# 3_mpcie.net
KiCad netlist of a schematic drawn in Altium Designer
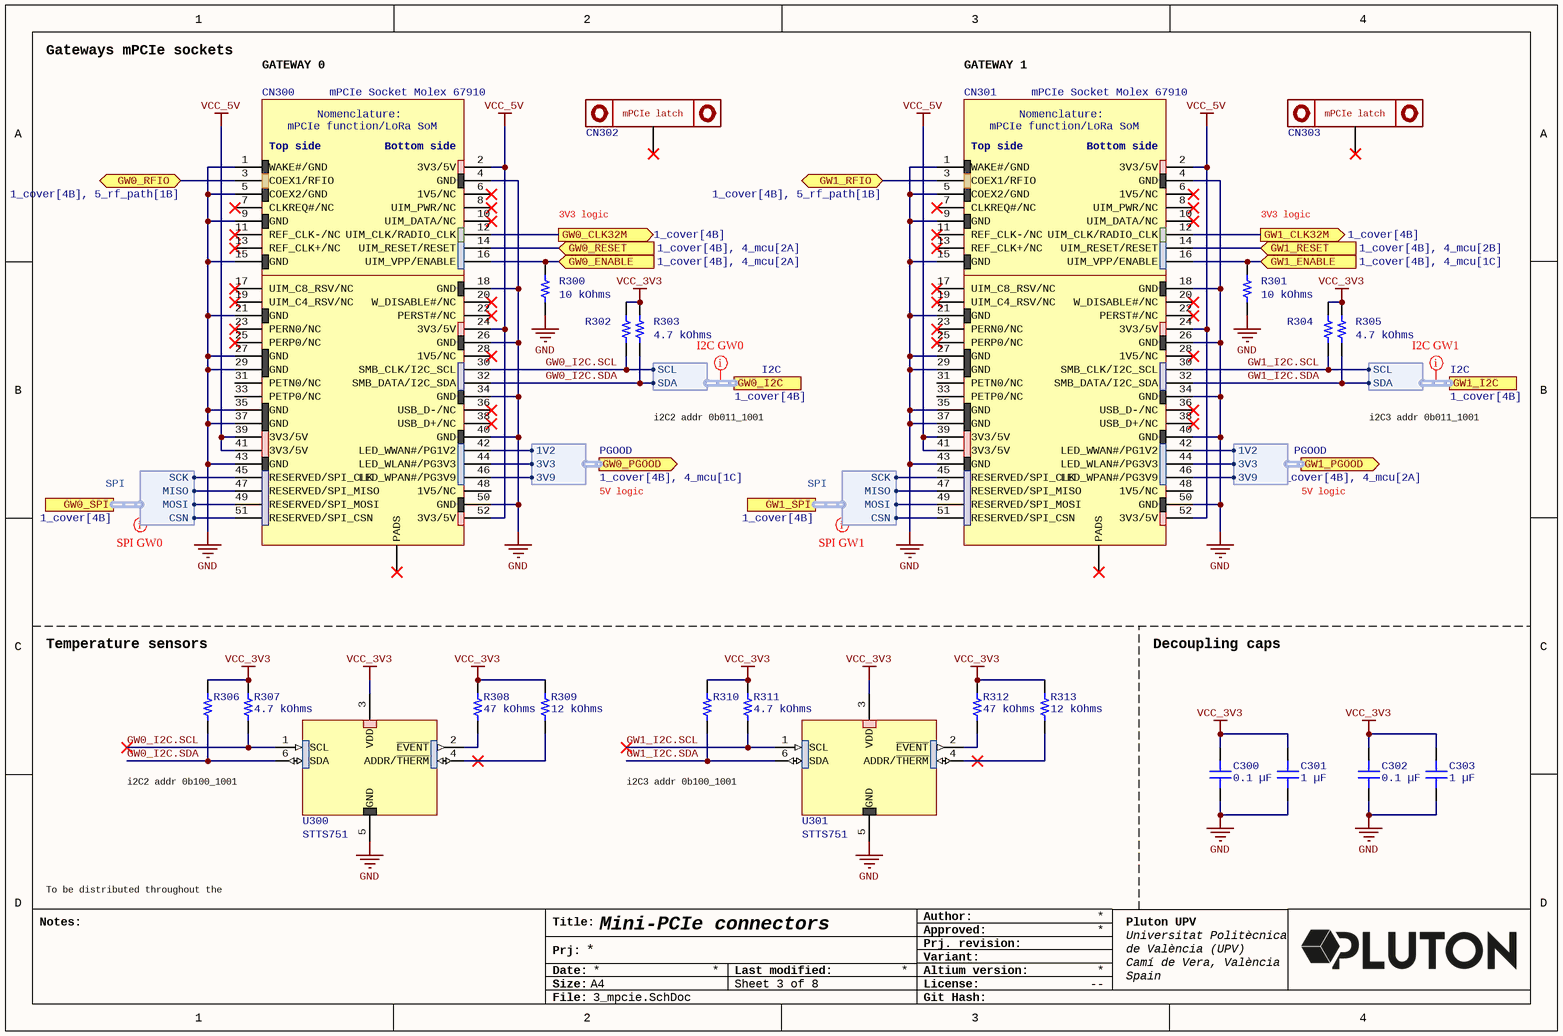
[diagram p0: 3_mpcie.SchDoc]

(export (version "E")
  (design (tool "Eeschema 10.0.6"))
  (components
    (comp (ref "C300")
      (value "0.1 µF")
      (footprint "CAP 0402_1005")
      (description "CAP CER 0402 0.1UF 16V X7R 10%")
      (fields (field (name "PART NUMBER") "C0402C104K4RECAUTO") (field (name "MANUFACTURER") "KEMET"))
      (libsource (lib "Celestial Altium Library - altium_library") (part "Capacitor"))
    )
    (comp (ref "C301")
      (value "1 µF")
      (footprint "CAP 0402_1005")
      (description "CAP CER 1UF 10V X7S 0402")
      (fields
        (field (name "PART NUMBER") "GRT155C71A105KE13D")
        (field (name "MANUFACTURER") "Murata Electronics")
      )
      (libsource (lib "Celestial Altium Library - altium_library") (part "Capacitor"))
    )
    (comp (ref "C302")
      (value "0.1 µF")
      (footprint "CAP 0402_1005")
      (description "CAP CER 0402 0.1UF 16V X7R 10%")
      (fields (field (name "PART NUMBER") "C0402C104K4RECAUTO") (field (name "MANUFACTURER") "KEMET"))
      (libsource (lib "Celestial Altium Library - altium_library") (part "Capacitor"))
    )
    (comp (ref "C303")
      (value "1 µF")
      (footprint "CAP 0402_1005")
      (description "CAP CER 1UF 10V X7S 0402")
      (fields
        (field (name "PART NUMBER") "GRT155C71A105KE13D")
        (field (name "MANUFACTURER") "Murata Electronics")
      )
      (libsource (lib "Celestial Altium Library - altium_library") (part "Capacitor"))
    )
    (comp (ref "CN300")
      (value "mPCIe Socket Molex 67910")
      (footprint "mpcie:mPCIe Socket Molex 67910")
      (libsource (lib "mpcie") (part "MiniPCIe Socket"))
    )
    (comp (ref "CN301")
      (value "mPCIe Socket Molex 67910")
      (footprint "mpcie:mPCIe Socket Molex 67910")
      (libsource (lib "mpcie") (part "MiniPCIe Socket"))
    )
    (comp (ref "CN302")
      (value "mPCIe Latch Molex 48099")
      (footprint "mpcie:MPCIE LATCH MOLEX 48099")
      (libsource (lib "mpcie") (part "MiniPCIe Socket latch"))
    )
    (comp (ref "CN303")
      (value "mPCIe Latch Molex 48099")
      (footprint "mpcie:MPCIE LATCH MOLEX 48099")
      (libsource (lib "mpcie") (part "MiniPCIe Socket latch"))
    )
    (comp (ref "R300")
      (value "10 kOhms")
      (footprint "RES 0201_0603")
      (description "RES SMD 10K OHM 1% 1/20W 0201")
      (fields (field (name "PART NUMBER") "AF0201FR-0710KL") (field (name "MANUFACTURER") "Yageo"))
      (libsource (lib "Celestial Altium Library - altium_library") (part "Resistor"))
    )
    (comp (ref "R301")
      (value "10 kOhms")
      (footprint "RES 0201_0603")
      (description "RES SMD 10K OHM 1% 1/20W 0201")
      (fields (field (name "PART NUMBER") "AF0201FR-0710KL") (field (name "MANUFACTURER") "Yageo"))
      (libsource (lib "Celestial Altium Library - altium_library") (part "Resistor"))
    )
    (comp (ref "R302")
      (value "4.7 kOhms")
      (footprint "RES 0201_0603")
      (description "RES SMD 4.7K OHM 1% 1/20W 0201")
      (fields (field (name "PART NUMBER") "AC0201FR-074K7L") (field (name "MANUFACTURER") "Yageo"))
      (libsource (lib "Celestial Altium Library - altium_library") (part "Resistor"))
    )
    (comp (ref "R303")
      (value "4.7 kOhms")
      (footprint "RES 0201_0603")
      (description "RES SMD 4.7K OHM 1% 1/20W 0201")
      (fields (field (name "PART NUMBER") "AC0201FR-074K7L") (field (name "MANUFACTURER") "Yageo"))
      (libsource (lib "Celestial Altium Library - altium_library") (part "Resistor"))
    )
    (comp (ref "R304")
      (value "4.7 kOhms")
      (footprint "RES 0201_0603")
      (description "RES SMD 4.7K OHM 1% 1/20W 0201")
      (fields (field (name "PART NUMBER") "AC0201FR-074K7L") (field (name "MANUFACTURER") "Yageo"))
      (libsource (lib "Celestial Altium Library - altium_library") (part "Resistor"))
    )
    (comp (ref "R305")
      (value "4.7 kOhms")
      (footprint "RES 0201_0603")
      (description "RES SMD 4.7K OHM 1% 1/20W 0201")
      (fields (field (name "PART NUMBER") "AC0201FR-074K7L") (field (name "MANUFACTURER") "Yageo"))
      (libsource (lib "Celestial Altium Library - altium_library") (part "Resistor"))
    )
    (comp (ref "R306")
      (value "4.7 kOhms")
      (footprint "RES 0201_0603")
      (description "RES SMD 4.7K OHM 1% 1/20W 0201")
      (fields (field (name "PART NUMBER") "AC0201FR-074K7L") (field (name "MANUFACTURER") "Yageo"))
      (libsource (lib "Celestial Altium Library - altium_library") (part "Resistor"))
    )
    (comp (ref "R307")
      (value "4.7 kOhms")
      (footprint "RES 0201_0603")
      (description "RES SMD 4.7K OHM 1% 1/20W 0201")
      (fields (field (name "PART NUMBER") "AC0201FR-074K7L") (field (name "MANUFACTURER") "Yageo"))
      (libsource (lib "Celestial Altium Library - altium_library") (part "Resistor"))
    )
    (comp (ref "R308")
      (value "47 kOhms")
      (footprint "RES 0201_0603")
      (description "RES SMD 47K OHM 1% 1/20W 0201")
      (fields (field (name "PART NUMBER") "AC0201FR-0747KL") (field (name "MANUFACTURER") "Yageo"))
      (libsource (lib "Celestial Altium Library - altium_library") (part "Resistor"))
    )
    (comp (ref "R309")
      (value "12 kOhms")
      (footprint "RES 0201_0603")
      (description "RES SMD 12K OHM 1% 1/20W 0201")
      (fields (field (name "PART NUMBER") "CRCW020112K0FNED") (field (name "MANUFACTURER") "Vishay Dale"))
      (libsource (lib "Celestial Altium Library - altium_library") (part "Resistor"))
    )
    (comp (ref "R310")
      (value "4.7 kOhms")
      (footprint "RES 0201_0603")
      (description "RES SMD 4.7K OHM 1% 1/20W 0201")
      (fields (field (name "PART NUMBER") "AC0201FR-074K7L") (field (name "MANUFACTURER") "Yageo"))
      (libsource (lib "Celestial Altium Library - altium_library") (part "Resistor"))
    )
    (comp (ref "R311")
      (value "4.7 kOhms")
      (footprint "RES 0201_0603")
      (description "RES SMD 4.7K OHM 1% 1/20W 0201")
      (fields (field (name "PART NUMBER") "AC0201FR-074K7L") (field (name "MANUFACTURER") "Yageo"))
      (libsource (lib "Celestial Altium Library - altium_library") (part "Resistor"))
    )
    (comp (ref "R312")
      (value "47 kOhms")
      (footprint "RES 0201_0603")
      (description "RES SMD 47K OHM 1% 1/20W 0201")
      (fields (field (name "PART NUMBER") "AC0201FR-0747KL") (field (name "MANUFACTURER") "Yageo"))
      (libsource (lib "Celestial Altium Library - altium_library") (part "Resistor"))
    )
    (comp (ref "R313")
      (value "12 kOhms")
      (footprint "RES 0201_0603")
      (description "RES SMD 12K OHM 1% 1/20W 0201")
      (fields (field (name "PART NUMBER") "CRCW020112K0FNED") (field (name "MANUFACTURER") "Vishay Dale"))
      (libsource (lib "Celestial Altium Library - altium_library") (part "Resistor"))
    )
    (comp (ref "U300")
      (value "STTS751")
      (footprint "ics:UDFN-6L")
      (description "2.25 V low-voltage local digital temperature sensor")
      (libsource (lib "sensors") (part "STTS751"))
    )
    (comp (ref "U301")
      (value "STTS751")
      (footprint "ics:UDFN-6L")
      (description "2.25 V low-voltage local digital temperature sensor")
      (libsource (lib "sensors") (part "STTS751"))
    )
  )
  (nets
    (net (code "4") (name "/GW0_CLK32M") (class "Default")
      (node (ref "CN300") (pin "12") (pinfunction "UIM_CLK/RADIO_CLK_12") (pintype "passive"))
    )
    (net (code "5") (name "/GW0_ENABLE") (class "Default")
      (node (ref "CN300") (pin "16") (pinfunction "UIM_VPP/ENABLE_16") (pintype "passive"))
      (node (ref "R300") (pin "2") (pinfunction "2_2") (pintype "passive"))
    )
    (net (code "6") (name "/GW0_I2C.SCL") (class "Default")
      (node (ref "CN300") (pin "30") (pinfunction "SMB_CLK/I2C_SCL_30") (pintype "passive"))
      (node (ref "R302") (pin "1") (pinfunction "1_1") (pintype "passive"))
      (node (ref "R307") (pin "1") (pinfunction "1_1") (pintype "passive"))
      (node (ref "U300") (pin "1") (pinfunction "SCL_1") (pintype "input"))
    )
    (net (code "7") (name "/GW0_I2C.SDA") (class "Default")
      (node (ref "CN300") (pin "32") (pinfunction "SMB_DATA/I2C_SDA_32") (pintype "passive"))
      (node (ref "R303") (pin "1") (pinfunction "1_1") (pintype "passive"))
      (node (ref "R306") (pin "1") (pinfunction "1_1") (pintype "passive"))
      (node (ref "U300") (pin "6") (pinfunction "SDA_6") (pintype "bidirectional"))
    )
    (net (code "8") (name "/GW0_RESET") (class "Default")
      (node (ref "CN300") (pin "14") (pinfunction "UIM_RESET/RESET_14") (pintype "passive"))
    )
    (net (code "9") (name "/GW0_RFIO") (class "Default")
      (node (ref "CN300") (pin "3") (pinfunction "COEX1/RFIO_3") (pintype "passive"))
    )
    (net (code "10") (name "/GW1_CLK32M") (class "Default")
      (node (ref "CN301") (pin "12") (pinfunction "UIM_CLK/RADIO_CLK_12") (pintype "passive"))
    )
    (net (code "11") (name "/GW1_ENABLE") (class "Default")
      (node (ref "CN301") (pin "16") (pinfunction "UIM_VPP/ENABLE_16") (pintype "passive"))
      (node (ref "R301") (pin "2") (pinfunction "2_2") (pintype "passive"))
    )
    (net (code "12") (name "/GW1_I2C.SCL") (class "Default")
      (node (ref "CN301") (pin "30") (pinfunction "SMB_CLK/I2C_SCL_30") (pintype "passive"))
      (node (ref "R304") (pin "1") (pinfunction "1_1") (pintype "passive"))
      (node (ref "R311") (pin "1") (pinfunction "1_1") (pintype "passive"))
      (node (ref "U301") (pin "1") (pinfunction "SCL_1") (pintype "input"))
    )
    (net (code "13") (name "/GW1_I2C.SDA") (class "Default")
      (node (ref "CN301") (pin "32") (pinfunction "SMB_DATA/I2C_SDA_32") (pintype "passive"))
      (node (ref "R305") (pin "1") (pinfunction "1_1") (pintype "passive"))
      (node (ref "R310") (pin "1") (pinfunction "1_1") (pintype "passive"))
      (node (ref "U301") (pin "6") (pinfunction "SDA_6") (pintype "bidirectional"))
    )
    (net (code "14") (name "/GW1_RESET") (class "Default")
      (node (ref "CN301") (pin "14") (pinfunction "UIM_RESET/RESET_14") (pintype "passive"))
    )
    (net (code "15") (name "/GW1_RFIO") (class "Default")
      (node (ref "CN301") (pin "3") (pinfunction "COEX1/RFIO_3") (pintype "passive"))
    )
    (net (code "19") (name "GND") (class "Default")
      (node (ref "C300") (pin "1") (pinfunction "1_1") (pintype "passive"))
      (node (ref "C301") (pin "1") (pinfunction "1_1") (pintype "passive"))
      (node (ref "C302") (pin "1") (pinfunction "1_1") (pintype "passive"))
      (node (ref "C303") (pin "1") (pinfunction "1_1") (pintype "passive"))
      (node (ref "CN300") (pin "1") (pinfunction "WAKE#/GND_1") (pintype "passive"))
      (node (ref "CN300") (pin "15") (pinfunction "GND_15") (pintype "power_in"))
      (node (ref "CN300") (pin "18") (pinfunction "GND_18") (pintype "power_in"))
      (node (ref "CN300") (pin "21") (pinfunction "GND_21") (pintype "power_in"))
      (node (ref "CN300") (pin "26") (pinfunction "GND_26") (pintype "power_in"))
      (node (ref "CN300") (pin "27") (pinfunction "GND_27") (pintype "power_in"))
      (node (ref "CN300") (pin "29") (pinfunction "GND_29") (pintype "power_in"))
      (node (ref "CN300") (pin "34") (pinfunction "GND_34") (pintype "power_in"))
      (node (ref "CN300") (pin "35") (pinfunction "GND_35") (pintype "power_in"))
      (node (ref "CN300") (pin "37") (pinfunction "GND_37") (pintype "power_in"))
      (node (ref "CN300") (pin "4") (pinfunction "GND_4") (pintype "power_in"))
      (node (ref "CN300") (pin "40") (pinfunction "GND_40") (pintype "power_in"))
      (node (ref "CN300") (pin "43") (pinfunction "GND_43") (pintype "power_in"))
      (node (ref "CN300") (pin "5") (pinfunction "COEX2/GND_5") (pintype "passive"))
      (node (ref "CN300") (pin "50") (pinfunction "GND_50") (pintype "power_in"))
      (node (ref "CN300") (pin "9") (pinfunction "GND_9") (pintype "power_in"))
      (node (ref "CN301") (pin "1") (pinfunction "WAKE#/GND_1") (pintype "passive"))
      (node (ref "CN301") (pin "15") (pinfunction "GND_15") (pintype "power_in"))
      (node (ref "CN301") (pin "18") (pinfunction "GND_18") (pintype "power_in"))
      (node (ref "CN301") (pin "21") (pinfunction "GND_21") (pintype "power_in"))
      (node (ref "CN301") (pin "26") (pinfunction "GND_26") (pintype "power_in"))
      (node (ref "CN301") (pin "27") (pinfunction "GND_27") (pintype "power_in"))
      (node (ref "CN301") (pin "29") (pinfunction "GND_29") (pintype "power_in"))
      (node (ref "CN301") (pin "34") (pinfunction "GND_34") (pintype "power_in"))
      (node (ref "CN301") (pin "35") (pinfunction "GND_35") (pintype "power_in"))
      (node (ref "CN301") (pin "37") (pinfunction "GND_37") (pintype "power_in"))
      (node (ref "CN301") (pin "4") (pinfunction "GND_4") (pintype "power_in"))
      (node (ref "CN301") (pin "40") (pinfunction "GND_40") (pintype "power_in"))
      (node (ref "CN301") (pin "43") (pinfunction "GND_43") (pintype "power_in"))
      (node (ref "CN301") (pin "5") (pinfunction "COEX2/GND_5") (pintype "passive"))
      (node (ref "CN301") (pin "50") (pinfunction "GND_50") (pintype "power_in"))
      (node (ref "CN301") (pin "9") (pinfunction "GND_9") (pintype "power_in"))
      (node (ref "R300") (pin "1") (pinfunction "1_1") (pintype "passive"))
      (node (ref "R301") (pin "1") (pinfunction "1_1") (pintype "passive"))
      (node (ref "U300") (pin "5") (pinfunction "GND_5") (pintype "power_in"))
      (node (ref "U301") (pin "5") (pinfunction "GND_5") (pintype "power_in"))
    )
    (net (code "20") (name "Net-(U300-ADDR{slash}~{THERM})") (class "Default")
      (node (ref "R309") (pin "1") (pinfunction "1_1") (pintype "passive"))
      (node (ref "U300") (pin "4") (pinfunction "ADDR/~{THERM}_4") (pintype "bidirectional"))
    )
    (net (code "21") (name "Net-(U300-~{EVENT})") (class "Default")
      (node (ref "R308") (pin "1") (pinfunction "1_1") (pintype "passive"))
      (node (ref "U300") (pin "2") (pinfunction "~{EVENT}_2") (pintype "output"))
    )
    (net (code "22") (name "Net-(U301-ADDR{slash}~{THERM})") (class "Default")
      (node (ref "R313") (pin "1") (pinfunction "1_1") (pintype "passive"))
      (node (ref "U301") (pin "4") (pinfunction "ADDR/~{THERM}_4") (pintype "bidirectional"))
    )
    (net (code "23") (name "Net-(U301-~{EVENT})") (class "Default")
      (node (ref "R312") (pin "1") (pinfunction "1_1") (pintype "passive"))
      (node (ref "U301") (pin "2") (pinfunction "~{EVENT}_2") (pintype "output"))
    )
    (net (code "24") (name "VCC_3V3") (class "Default")
      (node (ref "C300") (pin "2") (pinfunction "2_2") (pintype "passive"))
      (node (ref "C301") (pin "2") (pinfunction "2_2") (pintype "passive"))
      (node (ref "C302") (pin "2") (pinfunction "2_2") (pintype "passive"))
      (node (ref "C303") (pin "2") (pinfunction "2_2") (pintype "passive"))
      (node (ref "R302") (pin "2") (pinfunction "2_2") (pintype "passive"))
      (node (ref "R303") (pin "2") (pinfunction "2_2") (pintype "passive"))
      (node (ref "R304") (pin "2") (pinfunction "2_2") (pintype "passive"))
      (node (ref "R305") (pin "2") (pinfunction "2_2") (pintype "passive"))
      (node (ref "R306") (pin "2") (pinfunction "2_2") (pintype "passive"))
      (node (ref "R307") (pin "2") (pinfunction "2_2") (pintype "passive"))
      (node (ref "R308") (pin "2") (pinfunction "2_2") (pintype "passive"))
      (node (ref "R309") (pin "2") (pinfunction "2_2") (pintype "passive"))
      (node (ref "R310") (pin "2") (pinfunction "2_2") (pintype "passive"))
      (node (ref "R311") (pin "2") (pinfunction "2_2") (pintype "passive"))
      (node (ref "R312") (pin "2") (pinfunction "2_2") (pintype "passive"))
      (node (ref "R313") (pin "2") (pinfunction "2_2") (pintype "passive"))
      (node (ref "U300") (pin "3") (pinfunction "VDD_3") (pintype "power_in"))
      (node (ref "U301") (pin "3") (pinfunction "VDD_3") (pintype "power_in"))
    )
    (net (code "25") (name "VCC_5V") (class "Default")
      (node (ref "CN300") (pin "2") (pinfunction "3V3/5V_2") (pintype "passive"))
      (node (ref "CN300") (pin "24") (pinfunction "3V3/5V_24") (pintype "passive"))
      (node (ref "CN300") (pin "39") (pinfunction "3V3/5V_39") (pintype "passive"))
      (node (ref "CN300") (pin "41") (pinfunction "3V3/5V_41") (pintype "passive"))
      (node (ref "CN300") (pin "52") (pinfunction "3V3/5V_52") (pintype "passive"))
      (node (ref "CN301") (pin "2") (pinfunction "3V3/5V_2") (pintype "passive"))
      (node (ref "CN301") (pin "24") (pinfunction "3V3/5V_24") (pintype "passive"))
      (node (ref "CN301") (pin "39") (pinfunction "3V3/5V_39") (pintype "passive"))
      (node (ref "CN301") (pin "41") (pinfunction "3V3/5V_41") (pintype "passive"))
      (node (ref "CN301") (pin "52") (pinfunction "3V3/5V_52") (pintype "passive"))
    )
    (net (code "26") (name "unconnected-(CN300-1V5{slash}NC-Pad6)") (class "Default")
      (node (ref "CN300") (pin "6") (pinfunction "1V5/NC_6") (pintype "passive+no_connect"))
    )
    (net (code "27") (name "unconnected-(CN300-1V5{slash}NC-Pad28)") (class "Default")
      (node (ref "CN300") (pin "28") (pinfunction "1V5/NC_28") (pintype "power_in+no_connect"))
    )
    (net (code "28") (name "unconnected-(CN300-1V5{slash}NC-Pad48)") (class "Default")
      (node (ref "CN300") (pin "48") (pinfunction "1V5/NC_48") (pintype "passive"))
    )
    (net (code "29") (name "unconnected-(CN300-CLKREQ#{slash}NC-Pad7)") (class "Default")
      (node (ref "CN300") (pin "7") (pinfunction "CLKREQ#/NC_7") (pintype "passive+no_connect"))
    )
    (net (code "30") (name "unconnected-(CN300-LED_WLAN#{slash}PG3V3-Pad44)") (class "Default")
      (node (ref "CN300") (pin "44") (pinfunction "LED_WLAN#/PG3V3_44") (pintype "passive"))
    )
    (net (code "31") (name "unconnected-(CN300-LED_WPAN#{slash}PG3V9-Pad46)") (class "Default")
      (node (ref "CN300") (pin "46") (pinfunction "LED_WPAN#/PG3V9_46") (pintype "passive"))
    )
    (net (code "32") (name "unconnected-(CN300-LED_WWAN#{slash}PG1V2-Pad42)") (class "Default")
      (node (ref "CN300") (pin "42") (pinfunction "LED_WWAN#/PG1V2_42") (pintype "passive"))
    )
    (net (code "33") (name "unconnected-(CN300-PADS-Pad0)") (class "Default")
      (node (ref "CN300") (pin "0") (pinfunction "PADS_0") (pintype "passive+no_connect"))
    )
    (net (code "34") (name "unconnected-(CN300-PERN0{slash}NC-Pad23)") (class "Default")
      (node (ref "CN300") (pin "23") (pinfunction "PERN0/NC_23") (pintype "passive+no_connect"))
    )
    (net (code "35") (name "unconnected-(CN300-PERP0{slash}NC-Pad25)") (class "Default")
      (node (ref "CN300") (pin "25") (pinfunction "PERP0/NC_25") (pintype "passive+no_connect"))
    )
    (net (code "36") (name "unconnected-(CN300-PERST#{slash}NC-Pad22)") (class "Default")
      (node (ref "CN300") (pin "22") (pinfunction "PERST#/NC_22") (pintype "passive+no_connect"))
    )
    (net (code "37") (name "unconnected-(CN300-PETN0{slash}NC-Pad31)") (class "Default")
      (node (ref "CN300") (pin "31") (pinfunction "PETN0/NC_31") (pintype "passive"))
    )
    (net (code "38") (name "unconnected-(CN300-PETP0{slash}NC-Pad33)") (class "Default")
      (node (ref "CN300") (pin "33") (pinfunction "PETP0/NC_33") (pintype "passive"))
    )
    (net (code "39") (name "unconnected-(CN300-REF_CLK+{slash}NC-Pad13)") (class "Default")
      (node (ref "CN300") (pin "13") (pinfunction "REF_CLK+/NC_13") (pintype "passive+no_connect"))
    )
    (net (code "40") (name "unconnected-(CN300-REF_CLK-{slash}NC-Pad11)") (class "Default")
      (node (ref "CN300") (pin "11") (pinfunction "REF_CLK-/NC_11") (pintype "passive+no_connect"))
    )
    (net (code "41") (name "unconnected-(CN300-RESERVED{slash}SPI_CLK-Pad45)") (class "Default")
      (node (ref "CN300") (pin "45") (pinfunction "RESERVED/SPI_CLK_45") (pintype "passive"))
    )
    (net (code "42") (name "unconnected-(CN300-RESERVED{slash}SPI_CSN-Pad51)") (class "Default")
      (node (ref "CN300") (pin "51") (pinfunction "RESERVED/SPI_CSN_51") (pintype "passive"))
    )
    (net (code "43") (name "unconnected-(CN300-RESERVED{slash}SPI_MISO-Pad47)") (class "Default")
      (node (ref "CN300") (pin "47") (pinfunction "RESERVED/SPI_MISO_47") (pintype "passive"))
    )
    (net (code "44") (name "unconnected-(CN300-RESERVED{slash}SPI_MOSI-Pad49)") (class "Default")
      (node (ref "CN300") (pin "49") (pinfunction "RESERVED/SPI_MOSI_49") (pintype "passive"))
    )
    (net (code "45") (name "unconnected-(CN300-UIM_C4_RSV{slash}NC-Pad19)") (class "Default")
      (node (ref "CN300") (pin "19") (pinfunction "UIM_C4_RSV/NC_19") (pintype "passive+no_connect"))
    )
    (net (code "46") (name "unconnected-(CN300-UIM_C8_RSV{slash}NC-Pad17)") (class "Default")
      (node (ref "CN300") (pin "17") (pinfunction "UIM_C8_RSV/NC_17") (pintype "passive+no_connect"))
    )
    (net (code "47") (name "unconnected-(CN300-UIM_DATA{slash}NC-Pad10)") (class "Default")
      (node (ref "CN300") (pin "10") (pinfunction "UIM_DATA/NC_10") (pintype "passive+no_connect"))
    )
    (net (code "48") (name "unconnected-(CN300-UIM_PWR{slash}NC-Pad8)") (class "Default")
      (node (ref "CN300") (pin "8") (pinfunction "UIM_PWR/NC_8") (pintype "passive+no_connect"))
    )
    (net (code "49") (name "unconnected-(CN300-USB_D+{slash}NC-Pad38)") (class "Default")
      (node (ref "CN300") (pin "38") (pinfunction "USB_D+/NC_38") (pintype "passive+no_connect"))
    )
    (net (code "50") (name "unconnected-(CN300-USB_D-{slash}NC-Pad36)") (class "Default")
      (node (ref "CN300") (pin "36") (pinfunction "USB_D-/NC_36") (pintype "passive+no_connect"))
    )
    (net (code "51") (name "unconnected-(CN300-W_DISABLE#{slash}NC-Pad20)") (class "Default")
      (node (ref "CN300") (pin "20") (pinfunction "W_DISABLE#/NC_20") (pintype "passive+no_connect"))
    )
    (net (code "52") (name "unconnected-(CN301-1V5{slash}NC-Pad6)") (class "Default")
      (node (ref "CN301") (pin "6") (pinfunction "1V5/NC_6") (pintype "passive+no_connect"))
    )
    (net (code "53") (name "unconnected-(CN301-1V5{slash}NC-Pad28)") (class "Default")
      (node (ref "CN301") (pin "28") (pinfunction "1V5/NC_28") (pintype "power_in+no_connect"))
    )
    (net (code "54") (name "unconnected-(CN301-1V5{slash}NC-Pad48)") (class "Default")
      (node (ref "CN301") (pin "48") (pinfunction "1V5/NC_48") (pintype "passive"))
    )
    (net (code "55") (name "unconnected-(CN301-CLKREQ#{slash}NC-Pad7)") (class "Default")
      (node (ref "CN301") (pin "7") (pinfunction "CLKREQ#/NC_7") (pintype "passive+no_connect"))
    )
    (net (code "56") (name "unconnected-(CN301-LED_WLAN#{slash}PG3V3-Pad44)") (class "Default")
      (node (ref "CN301") (pin "44") (pinfunction "LED_WLAN#/PG3V3_44") (pintype "passive"))
    )
    (net (code "57") (name "unconnected-(CN301-LED_WPAN#{slash}PG3V9-Pad46)") (class "Default")
      (node (ref "CN301") (pin "46") (pinfunction "LED_WPAN#/PG3V9_46") (pintype "passive"))
    )
    (net (code "58") (name "unconnected-(CN301-LED_WWAN#{slash}PG1V2-Pad42)") (class "Default")
      (node (ref "CN301") (pin "42") (pinfunction "LED_WWAN#/PG1V2_42") (pintype "passive"))
    )
    (net (code "59") (name "unconnected-(CN301-PADS-Pad0)") (class "Default")
      (node (ref "CN301") (pin "0") (pinfunction "PADS_0") (pintype "passive+no_connect"))
    )
    (net (code "60") (name "unconnected-(CN301-PERN0{slash}NC-Pad23)") (class "Default")
      (node (ref "CN301") (pin "23") (pinfunction "PERN0/NC_23") (pintype "passive+no_connect"))
    )
    (net (code "61") (name "unconnected-(CN301-PERP0{slash}NC-Pad25)") (class "Default")
      (node (ref "CN301") (pin "25") (pinfunction "PERP0/NC_25") (pintype "passive+no_connect"))
    )
    (net (code "62") (name "unconnected-(CN301-PERST#{slash}NC-Pad22)") (class "Default")
      (node (ref "CN301") (pin "22") (pinfunction "PERST#/NC_22") (pintype "passive+no_connect"))
    )
    (net (code "63") (name "unconnected-(CN301-PETN0{slash}NC-Pad31)") (class "Default")
      (node (ref "CN301") (pin "31") (pinfunction "PETN0/NC_31") (pintype "passive"))
    )
    (net (code "64") (name "unconnected-(CN301-PETP0{slash}NC-Pad33)") (class "Default")
      (node (ref "CN301") (pin "33") (pinfunction "PETP0/NC_33") (pintype "passive"))
    )
    (net (code "65") (name "unconnected-(CN301-REF_CLK+{slash}NC-Pad13)") (class "Default")
      (node (ref "CN301") (pin "13") (pinfunction "REF_CLK+/NC_13") (pintype "passive+no_connect"))
    )
    (net (code "66") (name "unconnected-(CN301-REF_CLK-{slash}NC-Pad11)") (class "Default")
      (node (ref "CN301") (pin "11") (pinfunction "REF_CLK-/NC_11") (pintype "passive+no_connect"))
    )
    (net (code "67") (name "unconnected-(CN301-RESERVED{slash}SPI_CLK-Pad45)") (class "Default")
      (node (ref "CN301") (pin "45") (pinfunction "RESERVED/SPI_CLK_45") (pintype "passive"))
    )
    (net (code "68") (name "unconnected-(CN301-RESERVED{slash}SPI_CSN-Pad51)") (class "Default")
      (node (ref "CN301") (pin "51") (pinfunction "RESERVED/SPI_CSN_51") (pintype "passive"))
    )
    (net (code "69") (name "unconnected-(CN301-RESERVED{slash}SPI_MISO-Pad47)") (class "Default")
      (node (ref "CN301") (pin "47") (pinfunction "RESERVED/SPI_MISO_47") (pintype "passive"))
    )
    (net (code "70") (name "unconnected-(CN301-RESERVED{slash}SPI_MOSI-Pad49)") (class "Default")
      (node (ref "CN301") (pin "49") (pinfunction "RESERVED/SPI_MOSI_49") (pintype "passive"))
    )
    (net (code "71") (name "unconnected-(CN301-UIM_C4_RSV{slash}NC-Pad19)") (class "Default")
      (node (ref "CN301") (pin "19") (pinfunction "UIM_C4_RSV/NC_19") (pintype "passive+no_connect"))
    )
    (net (code "72") (name "unconnected-(CN301-UIM_C8_RSV{slash}NC-Pad17)") (class "Default")
      (node (ref "CN301") (pin "17") (pinfunction "UIM_C8_RSV/NC_17") (pintype "passive+no_connect"))
    )
    (net (code "73") (name "unconnected-(CN301-UIM_DATA{slash}NC-Pad10)") (class "Default")
      (node (ref "CN301") (pin "10") (pinfunction "UIM_DATA/NC_10") (pintype "passive+no_connect"))
    )
    (net (code "74") (name "unconnected-(CN301-UIM_PWR{slash}NC-Pad8)") (class "Default")
      (node (ref "CN301") (pin "8") (pinfunction "UIM_PWR/NC_8") (pintype "passive+no_connect"))
    )
    (net (code "75") (name "unconnected-(CN301-USB_D+{slash}NC-Pad38)") (class "Default")
      (node (ref "CN301") (pin "38") (pinfunction "USB_D+/NC_38") (pintype "passive+no_connect"))
    )
    (net (code "76") (name "unconnected-(CN301-USB_D-{slash}NC-Pad36)") (class "Default")
      (node (ref "CN301") (pin "36") (pinfunction "USB_D-/NC_36") (pintype "passive+no_connect"))
    )
    (net (code "77") (name "unconnected-(CN301-W_DISABLE#{slash}NC-Pad20)") (class "Default")
      (node (ref "CN301") (pin "20") (pinfunction "W_DISABLE#/NC_20") (pintype "passive+no_connect"))
    )
    (net (code "78") (name "unconnected-(CN302-Pad1)") (class "Default")
      (node (ref "CN302") (pin "1") (pinfunction "1_1") (pintype "passive+no_connect"))
    )
    (net (code "79") (name "unconnected-(CN303-Pad1)") (class "Default")
      (node (ref "CN303") (pin "1") (pinfunction "1_1") (pintype "passive+no_connect"))
    )
  )
)
